# Cell1_Balancing.net
KiCad netlist of a schematic drawn in Altium Designer
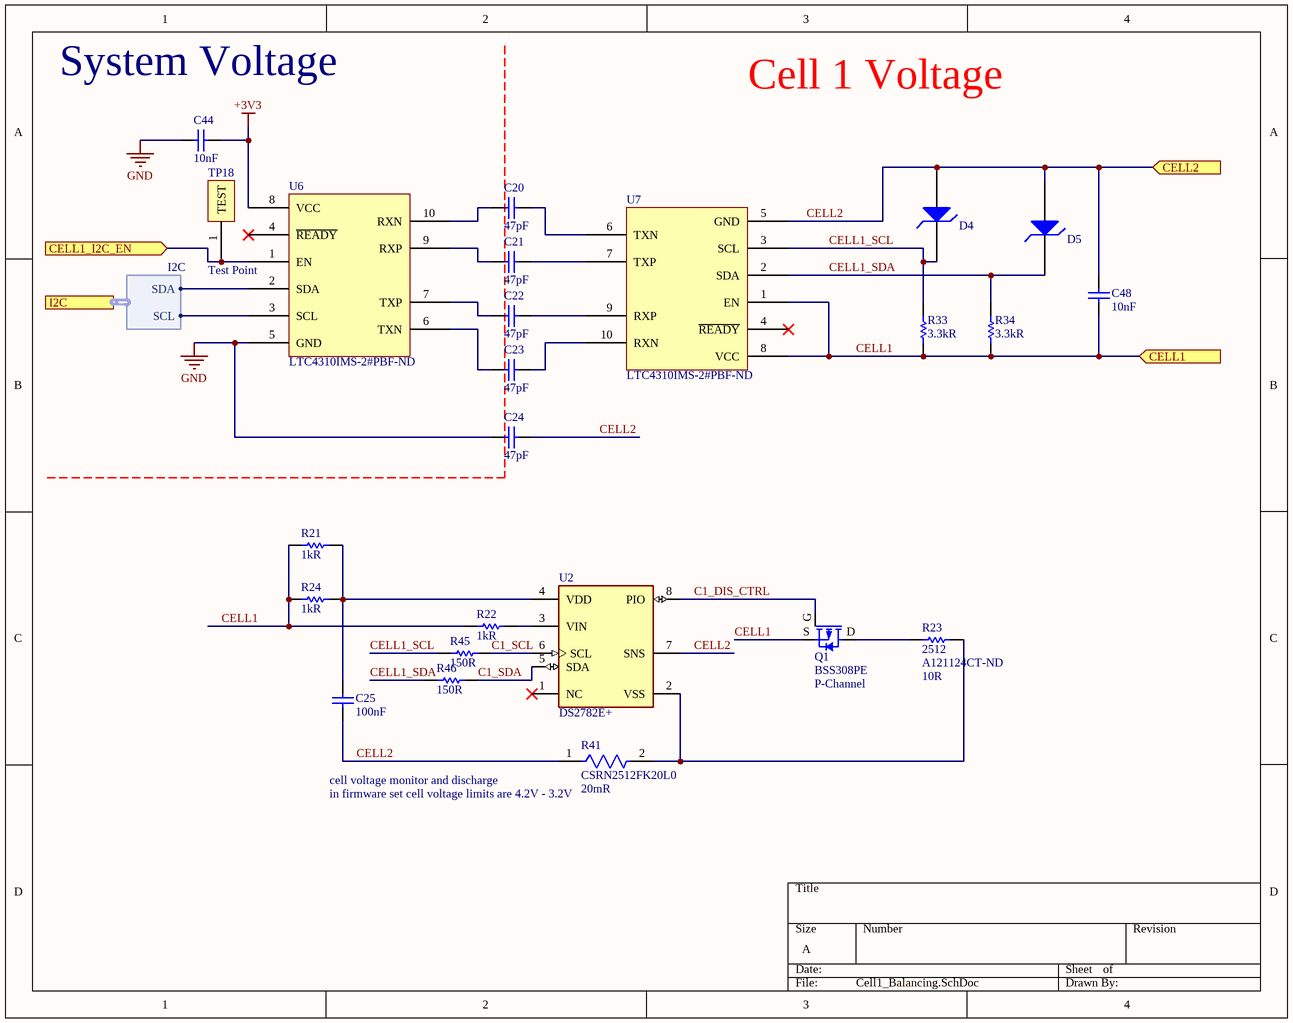
[diagram p0: Cell1_Balancing.SchDoc]

(export (version "E")
  (design (tool "Eeschema 10.0.6"))
  (components
    (comp (ref "C20")
      (value "06031A470FAT2A")
      (footprint "CAPC1608X90X35ML15T15")
      (fields (field (name "MANUFACTURER") "AVX Interconnect / Elco") (field (name "CAPACITANCE") "47pF"))
      (libsource (lib "Altium Content Vault") (part "CAP"))
    )
    (comp (ref "C21")
      (value "06031A470FAT2A")
      (footprint "CAPC1608X90X35ML15T15")
      (fields (field (name "MANUFACTURER") "AVX Interconnect / Elco") (field (name "CAPACITANCE") "47pF"))
      (libsource (lib "Altium Content Vault") (part "CAP"))
    )
    (comp (ref "C22")
      (value "06031A470FAT2A")
      (footprint "CAPC1608X90X35ML15T15")
      (fields (field (name "MANUFACTURER") "AVX Interconnect / Elco") (field (name "CAPACITANCE") "47pF"))
      (libsource (lib "Altium Content Vault") (part "CAP"))
    )
    (comp (ref "C23")
      (value "06031A470FAT2A")
      (footprint "CAPC1608X90X35ML15T15")
      (fields (field (name "MANUFACTURER") "AVX Interconnect / Elco") (field (name "CAPACITANCE") "47pF"))
      (libsource (lib "Altium Content Vault") (part "CAP"))
    )
    (comp (ref "C24")
      (value "06031A470FAT2A")
      (footprint "CAPC1608X90X35ML15T15")
      (fields (field (name "MANUFACTURER") "AVX Interconnect / Elco") (field (name "CAPACITANCE") "47pF"))
      (libsource (lib "Altium Content Vault") (part "CAP"))
    )
    (comp (ref "C25")
      (value "Capacitor 0402")
      (footprint "C0402")
      (description "CAP CER 0.1UF 25V X5R 0402 / High Value Multilayer Ceramic Capacitors (High dielectric type)")
      (fields
        (field (name "MANUFACTURER") "Taiyo Yuden")
        (field (name "MANUFACTURER PART NUMBER") "TMK105BJ104KV-F")
        (field (name "CAPACITANCE") "100nF")
      )
      (libsource (lib "Wally_BMS") (part "Capacitor 0402"))
    )
    (comp (ref "C44")
      (value "Capacitor 0402")
      (footprint "C0402")
      (description "Cap Ceramic 0.01uF 25V X7R 10% Pad SMD 0402 125C T/R")
      (fields
        (field (name "MANUFACTURER") "Samsung")
        (field (name "MANUFACTURER PART NUMBER") "CL05B103KA5NNNC")
        (field (name "CAPACITANCE") "10nF")
      )
      (libsource (lib "Wally_BMS") (part "Capacitor 0402"))
    )
    (comp (ref "C48")
      (value "Capacitor 0402")
      (footprint "C0402")
      (description "Cap Ceramic 0.01uF 25V X7R 10% Pad SMD 0402 125C T/R")
      (fields
        (field (name "MANUFACTURER") "Samsung")
        (field (name "MANUFACTURER PART NUMBER") "CL05B103KA5NNNC")
        (field (name "CAPACITANCE") "10nF")
      )
      (libsource (lib "Wally_BMS") (part "Capacitor 0402"))
    )
    (comp (ref "D4")
      (value "BZT52C4V7LP-7")
      (footprint "bzt52c4v7lp-7")
      (description "BZT52C4V7LP Series 4.7 V 10 mA Surface Mount Zener Diode - DFN1006-2")
      (fields (field (name "MANUFACTURER") "Diodes") (field (name "TOLERANCE") "6%"))
      (libsource (lib "Wally_BMS") (part "BZT52C4V7LP-7"))
    )
    (comp (ref "D5")
      (value "BZT52C4V7LP-7")
      (footprint "bzt52c4v7lp-7")
      (description "BZT52C4V7LP Series 4.7 V 10 mA Surface Mount Zener Diode - DFN1006-2")
      (fields (field (name "MANUFACTURER") "Diodes") (field (name "TOLERANCE") "6%"))
      (libsource (lib "Wally_BMS") (part "BZT52C4V7LP-7"))
    )
    (comp (ref "Q1")
      (value "BSS308PE")
      (footprint "BSS308PE")
      (description "MOSFET P-CH 30V 2A SOT23")
      (fields (field (name "FET TYPE") "P-Channel"))
      (libsource (lib "Transistors") (part "BSS308PE"))
    )
    (comp (ref "R21")
      (value "Resistor 0402")
      (footprint "RES0402")
      (description "Res Thick Film 0402 1K Ohm 1% 0.063W(1/16W) ±100ppm/C Pad SMD Automotive T/R")
      (fields
        (field (name "MANUFACTURER") "Stackpole Electronics")
        (field (name "MANUFACTURER PART NUMBER") "RMCF0402FT1K00")
        (field (name "RESISTANCE") "1kR")
      )
      (libsource (lib "Wally_BMS") (part "Resistor 0402"))
    )
    (comp (ref "R22")
      (value "Resistor 0402")
      (footprint "RES0402")
      (description "Res Thick Film 0402 1K Ohm 1% 0.063W(1/16W) ±100ppm/C Pad SMD Automotive T/R")
      (fields
        (field (name "MANUFACTURER") "Stackpole Electronics")
        (field (name "MANUFACTURER PART NUMBER") "RMCF0402FT1K00")
        (field (name "RESISTANCE") "1kR")
      )
      (libsource (lib "Wally_BMS") (part "Resistor 0402"))
    )
    (comp (ref "R23")
      (value "Resistor 2512")
      (footprint "RES2512")
      (fields
        (field (name "PACKAGE / CASE") "2512")
        (field (name "SUPPLIER PART NUMBER 1") "A121124CT-ND")
        (field (name "MANUFACTURER") "TE Connectivity CGS")
        (field (name "MANUFACTURER PART NUMBER") "1-2176230-4")
        (field (name "RESISTANCE") "10R")
        (field (name "TOLERANCE") "5%")
      )
      (libsource (lib "Wally_BMS") (part "Resistor 2512"))
    )
    (comp (ref "R24")
      (value "Resistor 0402")
      (footprint "RES0402")
      (description "Res Thick Film 0402 1K Ohm 1% 0.063W(1/16W) ±100ppm/C Pad SMD Automotive T/R")
      (fields
        (field (name "MANUFACTURER") "Stackpole Electronics")
        (field (name "MANUFACTURER PART NUMBER") "RMCF0402FT1K00")
        (field (name "RESISTANCE") "1kR")
      )
      (libsource (lib "Wally_BMS") (part "Resistor 0402"))
    )
    (comp (ref "R33")
      (value "Resistor 0402")
      (footprint "RES0402")
      (description "Res Thin Film 0402 3.3K Ohm 1% 1/16W ±50ppm/°C Molded SMD SMD Paper T/R")
      (fields
        (field (name "MANUFACTURER") "Yageo")
        (field (name "MANUFACTURER PART NUMBER") "RT0402FRE073K3L")
        (field (name "RESISTANCE") "3.3kR")
      )
      (libsource (lib "Wally_BMS") (part "Resistor 0402"))
    )
    (comp (ref "R34")
      (value "Resistor 0402")
      (footprint "RES0402")
      (description "Res Thin Film 0402 3.3K Ohm 1% 1/16W ±50ppm/°C Molded SMD SMD Paper T/R")
      (fields
        (field (name "MANUFACTURER") "Yageo")
        (field (name "MANUFACTURER PART NUMBER") "RT0402FRE073K3L")
        (field (name "RESISTANCE") "3.3kR")
      )
      (libsource (lib "Wally_BMS") (part "Resistor 0402"))
    )
    (comp (ref "R41")
      (value "CSRN2512FK20L0")
      (footprint "FP-CSRN2512-IPC_C")
      (description "Res Thick Film 2512 20mΩ 1% 2W ±200ppm/°C Molded SMD Plastic T/R")
      (fields (field (name "RESISTANCE") "20mR") (field (name "TOLERANCE") "1%"))
      (libsource (lib "Altium Content Vault") (part "1029c3af85768c4190bb7ad29bc67b5"))
    )
    (comp (ref "R45")
      (value "Resistor 0402")
      (footprint "RES0402")
      (description "Res Thin Film 0402 150 Ohm 1% 1/16W ±50ppm/°C Molded SMD SMD Paper T/R")
      (fields
        (field (name "MANUFACTURER") "Yageo")
        (field (name "MANUFACTURER PART NUMBER") "RT0402FRE07150RL")
        (field (name "RESISTANCE") "150R")
      )
      (libsource (lib "Wally_BMS") (part "Resistor 0402"))
    )
    (comp (ref "R46")
      (value "Resistor 0402")
      (footprint "RES0402")
      (description "Res Thin Film 0402 150 Ohm 1% 1/16W ±50ppm/°C Molded SMD SMD Paper T/R")
      (fields
        (field (name "MANUFACTURER") "Yageo")
        (field (name "MANUFACTURER PART NUMBER") "RT0402FRE07150RL")
        (field (name "RESISTANCE") "150R")
      )
      (libsource (lib "Wally_BMS") (part "Resistor 0402"))
    )
    (comp (ref "TP18")
      (value "Test Point")
      (footprint "TEST POINT")
      (libsource (lib "Wally_BMS") (part "Test Point"))
    )
    (comp (ref "U2")
      (value "DS2782E+")
      (footprint "FP-H8-2-MFG")
      (description "IC FUEL GAUGE BATT 8TSSOP")
      (fields
        (field (name "OCTOPART") "https://octopart.com/ds2782e%2B-maxim+integrated-8045252")
        (field (name "MANUFACTURER") "Maxim")
      )
      (libsource (lib "Altium Content Vault") (part "f9098ddd067e7739cd521d50be25c58"))
    )
    (comp (ref "U6")
      (value "LTC4310IMS-2#PBF-ND")
      (footprint "MSOP-10_MS_LIT")
      (description "DIGITAL ISOLATOR 2CH I2C 10MSOP")
      (libsource (lib "Wally_BMS") (part "LTC4310IMS-2#PBF"))
    )
    (comp (ref "U7")
      (value "LTC4310IMS-2#PBF-ND")
      (footprint "MSOP-10_MS_LIT")
      (description "DIGITAL ISOLATOR 2CH I2C 10MSOP")
      (libsource (lib "") (part "LTC4310IMS-2#PBF_1"))
    )
  )
  (nets
    (net (code "2") (name "+3V3") (class "Default")
      (node (ref "C44") (pin "1") (pinfunction "1_1") (pintype "passive"))
      (node (ref "U6") (pin "8") (pinfunction "VCC_8") (pintype "passive"))
    )
    (net (code "3") (name "/C1_DIS_CTRL") (class "Default")
      (node (ref "Q1") (pin "G") (pinfunction "G_G") (pintype "passive"))
      (node (ref "U2") (pin "8") (pinfunction "PIO_8") (pintype "bidirectional"))
    )
    (net (code "4") (name "/C1_SCL") (class "Default")
      (node (ref "R45") (pin "1") (pinfunction "1_1") (pintype "passive"))
      (node (ref "U2") (pin "6") (pinfunction "SCL_6") (pintype "input"))
    )
    (net (code "5") (name "/C1_SDA") (class "Default")
      (node (ref "R46") (pin "1") (pinfunction "1_1") (pintype "passive"))
      (node (ref "U2") (pin "5") (pinfunction "SDA_5") (pintype "bidirectional"))
    )
    (net (code "6") (name "/CELL1") (class "Default")
      (node (ref "C48") (pin "2") (pinfunction "2_2") (pintype "passive"))
      (node (ref "Q1") (pin "S") (pinfunction "3_S") (pintype "passive"))
      (node (ref "R21") (pin "1") (pinfunction "1_1") (pintype "passive"))
      (node (ref "R22") (pin "1") (pinfunction "1_1") (pintype "passive"))
      (node (ref "R24") (pin "1") (pinfunction "1_1") (pintype "passive"))
      (node (ref "R33") (pin "1") (pinfunction "1_1") (pintype "passive"))
      (node (ref "R34") (pin "1") (pinfunction "1_1") (pintype "passive"))
      (node (ref "U7") (pin "1") (pinfunction "EN_1") (pintype "passive"))
      (node (ref "U7") (pin "8") (pinfunction "VCC_8") (pintype "passive"))
    )
    (net (code "7") (name "/CELL1_I2C_EN") (class "Default")
      (node (ref "TP18") (pin "1") (pinfunction "TEST_1") (pintype "passive"))
      (node (ref "U6") (pin "1") (pinfunction "EN_1") (pintype "passive"))
    )
    (net (code "8") (name "/CELL1_SCL") (class "Default")
      (node (ref "D4") (pin "1") (pinfunction "K_1") (pintype "passive"))
      (node (ref "R33") (pin "2") (pinfunction "2_2") (pintype "passive"))
      (node (ref "R45") (pin "2") (pinfunction "2_2") (pintype "passive"))
      (node (ref "U7") (pin "3") (pinfunction "SCL_3") (pintype "passive"))
    )
    (net (code "9") (name "/CELL1_SDA") (class "Default")
      (node (ref "D5") (pin "1") (pinfunction "K_1") (pintype "passive"))
      (node (ref "R34") (pin "2") (pinfunction "2_2") (pintype "passive"))
      (node (ref "R46") (pin "2") (pinfunction "2_2") (pintype "passive"))
      (node (ref "U7") (pin "2") (pinfunction "SDA_2") (pintype "passive"))
    )
    (net (code "10") (name "/CELL2") (class "Default")
      (node (ref "C24") (pin "2") (pinfunction "2_2") (pintype "passive"))
      (node (ref "C25") (pin "1") (pinfunction "1_1") (pintype "passive"))
      (node (ref "C48") (pin "1") (pinfunction "1_1") (pintype "passive"))
      (node (ref "D4") (pin "2") (pinfunction "A_2") (pintype "passive"))
      (node (ref "D5") (pin "2") (pinfunction "A_2") (pintype "passive"))
      (node (ref "R41") (pin "1") (pinfunction "1_1") (pintype "passive"))
      (node (ref "U2") (pin "7") (pinfunction "SNS_7") (pintype "passive"))
      (node (ref "U7") (pin "5") (pinfunction "GND_5") (pintype "passive"))
    )
    (net (code "11") (name "/SCL") (class "Default")
      (node (ref "U6") (pin "3") (pinfunction "SCL_3") (pintype "passive"))
    )
    (net (code "12") (name "/SDA") (class "Default")
      (node (ref "U6") (pin "2") (pinfunction "SDA_2") (pintype "passive"))
    )
    (net (code "14") (name "GND") (class "Default")
      (node (ref "C24") (pin "1") (pinfunction "1_1") (pintype "passive"))
      (node (ref "C44") (pin "2") (pinfunction "2_2") (pintype "passive"))
      (node (ref "U6") (pin "5") (pinfunction "GND_5") (pintype "passive"))
    )
    (net (code "15") (name "Net-(Q1-PadD)") (class "Default")
      (node (ref "Q1") (pin "D") (pinfunction "D_D") (pintype "passive"))
      (node (ref "R23") (pin "1") (pinfunction "1_1") (pintype "passive"))
    )
    (net (code "16") (name "Net-(U2-VDD)") (class "Default")
      (node (ref "C25") (pin "2") (pinfunction "2_2") (pintype "passive"))
      (node (ref "R21") (pin "2") (pinfunction "2_2") (pintype "passive"))
      (node (ref "R24") (pin "2") (pinfunction "2_2") (pintype "passive"))
      (node (ref "U2") (pin "4") (pinfunction "VDD_4") (pintype "power_in"))
    )
    (net (code "17") (name "Net-(U2-VIN)") (class "Default")
      (node (ref "R22") (pin "2") (pinfunction "2_2") (pintype "passive"))
      (node (ref "U2") (pin "3") (pinfunction "VIN_3") (pintype "passive"))
    )
    (net (code "18") (name "Net-(U2-VSS)") (class "Default")
      (node (ref "R23") (pin "2") (pinfunction "2_2") (pintype "passive"))
      (node (ref "R41") (pin "2") (pinfunction "2_2") (pintype "passive"))
      (node (ref "U2") (pin "2") (pinfunction "VSS_2") (pintype "power_in"))
    )
    (net (code "19") (name "Net-(U6-RXN)") (class "Default")
      (node (ref "C20") (pin "1") (pinfunction "1_1") (pintype "passive"))
      (node (ref "U6") (pin "10") (pinfunction "RXN_10") (pintype "passive"))
    )
    (net (code "20") (name "Net-(U6-RXP)") (class "Default")
      (node (ref "C21") (pin "1") (pinfunction "1_1") (pintype "passive"))
      (node (ref "U6") (pin "9") (pinfunction "RXP_9") (pintype "passive"))
    )
    (net (code "21") (name "Net-(U6-TXN)") (class "Default")
      (node (ref "C23") (pin "1") (pinfunction "1_1") (pintype "passive"))
      (node (ref "U6") (pin "6") (pinfunction "TXN_6") (pintype "passive"))
    )
    (net (code "22") (name "Net-(U6-TXP)") (class "Default")
      (node (ref "C22") (pin "1") (pinfunction "1_1") (pintype "passive"))
      (node (ref "U6") (pin "7") (pinfunction "TXP_7") (pintype "passive"))
    )
    (net (code "23") (name "Net-(U7-RXN)") (class "Default")
      (node (ref "C23") (pin "2") (pinfunction "2_2") (pintype "passive"))
      (node (ref "U7") (pin "10") (pinfunction "RXN_10") (pintype "passive"))
    )
    (net (code "24") (name "Net-(U7-RXP)") (class "Default")
      (node (ref "C22") (pin "2") (pinfunction "2_2") (pintype "passive"))
      (node (ref "U7") (pin "9") (pinfunction "RXP_9") (pintype "passive"))
    )
    (net (code "25") (name "Net-(U7-TXN)") (class "Default")
      (node (ref "C20") (pin "2") (pinfunction "2_2") (pintype "passive"))
      (node (ref "U7") (pin "6") (pinfunction "TXN_6") (pintype "passive"))
    )
    (net (code "26") (name "Net-(U7-TXP)") (class "Default")
      (node (ref "C21") (pin "2") (pinfunction "2_2") (pintype "passive"))
      (node (ref "U7") (pin "7") (pinfunction "TXP_7") (pintype "passive"))
    )
    (net (code "27") (name "unconnected-(U2-NC-Pad1)") (class "Default")
      (node (ref "U2") (pin "1") (pinfunction "NC_1") (pintype "passive+no_connect"))
    )
    (net (code "28") (name "unconnected-(U6-~{READY}-Pad4)") (class "Default")
      (node (ref "U6") (pin "4") (pinfunction "~{READY}_4") (pintype "passive+no_connect"))
    )
    (net (code "29") (name "unconnected-(U7-~{READY}-Pad4)") (class "Default")
      (node (ref "U7") (pin "4") (pinfunction "~{READY}_4") (pintype "passive+no_connect"))
    )
  )
)
